# Sheet1.net
KiCad netlist of a schematic drawn in Altium Designer
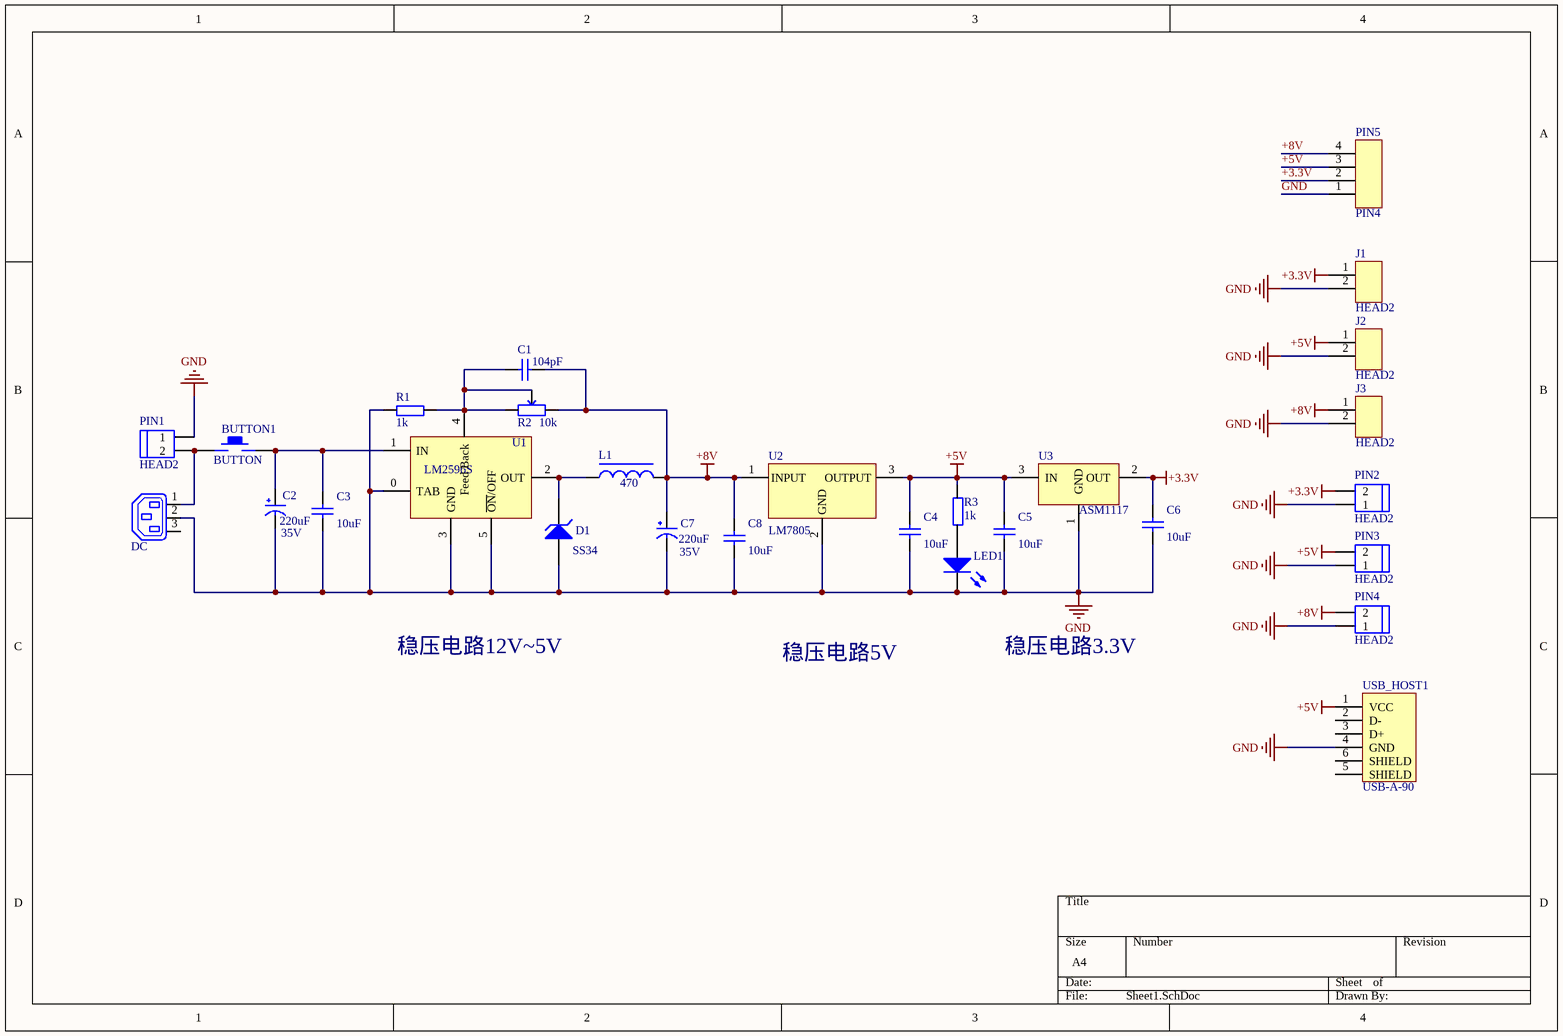
[diagram p0: Sheet1.SchDoc]

(export (version "E")
  (design (tool "Eeschema 10.0.6"))
  (components
    (comp (ref "BUTTON1")
      (value "BUTTON")
      (footprint "BOUTTON")
      (description "船式开关(KCD11 两档2脚)")
      (libsource (lib "STM32F429") (part "BUTTON"))
    )
    (comp (ref "C1")
      (value "104pF")
      (footprint "C-0805")
      (description "0805电容")
      (fields (field (name "Comment") "C_0805") (field (name "PUBLISHER") "Altium Limited"))
      (libsource (lib "Schlib1") (part "C_0805"))
    )
    (comp (ref "C2")
      (value "220uF")
      (footprint "8mm CAP+")
      (description "电解电容 35V 220 uF (8*10.2)")
      (fields (field (name "VOLTAGE") "35V"))
      (libsource (lib "Schlib1") (part "CAP+  8MM_1"))
    )
    (comp (ref "C3")
      (value "10uF")
      (footprint "C-0805")
      (description "0805电容")
      (fields (field (name "Comment") "C_0805") (field (name "PUBLISHER") "Altium Limited"))
      (libsource (lib "Schlib1") (part "C_0805"))
    )
    (comp (ref "C4")
      (value "10uF")
      (footprint "C-0805")
      (description "0805电容")
      (fields (field (name "Comment") "C_0805") (field (name "PUBLISHER") "Altium Limited"))
      (libsource (lib "Schlib1") (part "C_0805"))
    )
    (comp (ref "C5")
      (value "10uF")
      (footprint "C-0805")
      (description "0805电容")
      (fields (field (name "Comment") "C_0805") (field (name "PUBLISHER") "Altium Limited"))
      (libsource (lib "Schlib1") (part "C_0805"))
    )
    (comp (ref "C6")
      (value "10uF")
      (footprint "C-0805")
      (description "0805电容")
      (fields (field (name "Comment") "C_0805") (field (name "PUBLISHER") "Altium Limited"))
      (libsource (lib "Schlib1") (part "C_0805"))
    )
    (comp (ref "C7")
      (value "220uF")
      (footprint "8mm CAP+")
      (description "电解电容 35V 220 uF (8*10.2)")
      (fields (field (name "VOLTAGE") "35V"))
      (libsource (lib "Schlib1") (part "CAP+  8MM_1"))
    )
    (comp (ref "C8")
      (value "10uF")
      (footprint "C-0805")
      (description "0805电容")
      (fields (field (name "Comment") "C_0805") (field (name "PUBLISHER") "Altium Limited"))
      (libsource (lib "Schlib1") (part "C_0805"))
    )
    (comp (ref "D1")
      (value "SS34")
      (footprint "Diode-SS14")
      (description "稳压二极管 SS34（214A）")
      (fields (field (name "PUBLISHER") "Altium Limited"))
      (libsource (lib "Schlib1") (part "D Zener"))
    )
    (comp (ref "DC1")
      (value "DC")
      (footprint "DC-DC接口")
      (description "DC 电源插座 (5.5-2.1)")
      (libsource (lib "STM32F429") (part "DC"))
    )
    (comp (ref "J1")
      (value "HEAD2")
      (footprint "HEARD2")
      (description "2pin的连接键")
      (libsource (lib "SchlibCreativeDesign") (part "HEAD2"))
    )
    (comp (ref "J2")
      (value "HEAD2")
      (footprint "HEARD2")
      (description "2pin的连接键")
      (libsource (lib "SchlibCreativeDesign") (part "HEAD2"))
    )
    (comp (ref "J3")
      (value "HEAD2")
      (footprint "HEARD2")
      (description "2pin的连接键")
      (libsource (lib "SchlibCreativeDesign") (part "HEAD2"))
    )
    (comp (ref "L1")
      (value "470")
      (footprint "L")
      (description "Inductor")
      (fields (field (name "PUBLISHER") "Altium Limited"))
      (libsource (lib "Schlib1") (part "L"))
    )
    (comp (ref "LED1")
      (value "LED_0805")
      (footprint "LED-0805")
      (description "0805-LED")
      (fields (field (name "PUBLISHER") "Altium Limited"))
      (libsource (lib "Schlib1") (part "LED 0805"))
    )
    (comp (ref "PIN1")
      (value "HEAD2")
      (footprint "2PIN")
      (description "接线端子(KF301 2P)")
      (libsource (lib "STM32F429") (part "HEAD2"))
    )
    (comp (ref "PIN2") (value "HEAD2") (footprint "2PIN") (libsource (lib "STM32F429") (part "HEAD2")))
    (comp (ref "PIN3") (value "HEAD2") (footprint "2PIN") (libsource (lib "STM32F429") (part "HEAD2")))
    (comp (ref "PIN4") (value "HEAD2") (footprint "2PIN") (libsource (lib "STM32F429") (part "HEAD2")))
    (comp (ref "PIN5") (value "PIN4") (footprint "HDR4") (libsource (lib "Schlib1") (part "PIN4")))
    (comp (ref "R1")
      (value "1k")
      (footprint "R-0805")
      (description "0805电阻")
      (fields (field (name "Comment") "0805"))
      (libsource (lib "Schlib1") (part "R_0805"))
    )
    (comp (ref "R2")
      (value "10k")
      (footprint "RESPACK")
      (description "3296W电位器")
      (fields (field (name "Comment") "Slide rheostat"))
      (libsource (lib "Schlib1") (part "Slide rheostat"))
    )
    (comp (ref "R3")
      (value "1k")
      (footprint "R-0805")
      (description "0805电阻")
      (fields (field (name "Comment") "0805"))
      (libsource (lib "Schlib1") (part "R_0805"))
    )
    (comp (ref "U1")
      (value "LM2596S")
      (footprint "LM2596S")
      (description "LM2596S稳压芯片")
      (libsource (lib "Schlib1") (part "LM2596S_1"))
    )
    (comp (ref "U2")
      (value "LM7805")
      (footprint "LM7805")
      (description "LM7805三端稳压芯片")
      (libsource (lib "Schlib1") (part "LM7805"))
    )
    (comp (ref "U3")
      (value "ASM1117")
      (footprint "ASM1117")
      (description "ASM1117三端稳压芯片")
      (libsource (lib "Schlib1") (part "ASM1117"))
    )
    (comp (ref "USB_HOST1")
      (value "USB-A-90")
      (footprint "USB-A-90")
      (libsource (lib "ThirdShaft") (part "USB_A_90_1"))
    )
  )
  (nets
    (net (code "1") (name "+3.3V") (class "Default")
      (node (ref "C6") (pin "2") (pinfunction "2_2") (pintype "passive"))
      (node (ref "J1") (pin "1") (pinfunction "1_1") (pintype "passive"))
      (node (ref "PIN2") (pin "2") (pinfunction "2_2") (pintype "passive"))
      (node (ref "PIN5") (pin "2") (pinfunction "2_2") (pintype "passive"))
      (node (ref "U3") (pin "2") (pinfunction "OUT_2") (pintype "passive"))
    )
    (net (code "2") (name "+5V") (class "Default")
      (node (ref "C4") (pin "2") (pinfunction "2_2") (pintype "passive"))
      (node (ref "C5") (pin "2") (pinfunction "2_2") (pintype "passive"))
      (node (ref "J2") (pin "1") (pinfunction "1_1") (pintype "passive"))
      (node (ref "PIN3") (pin "2") (pinfunction "2_2") (pintype "passive"))
      (node (ref "PIN5") (pin "3") (pinfunction "3_3") (pintype "passive"))
      (node (ref "R3") (pin "2") (pintype "passive"))
      (node (ref "U2") (pin "3") (pinfunction "OUTPUT_3") (pintype "passive"))
      (node (ref "U3") (pin "3") (pinfunction "IN_3") (pintype "passive"))
      (node (ref "USB_HOST1") (pin "1") (pinfunction "VCC_1") (pintype "passive"))
    )
    (net (code "3") (name "+8V") (class "Default")
      (node (ref "C1") (pin "1") (pinfunction "1_1") (pintype "passive"))
      (node (ref "C7") (pin "1") (pinfunction "VCC_1") (pintype "passive"))
      (node (ref "C8") (pin "2") (pinfunction "2_2") (pintype "passive"))
      (node (ref "J3") (pin "1") (pinfunction "1_1") (pintype "passive"))
      (node (ref "L1") (pin "2") (pinfunction "2_2") (pintype "passive"))
      (node (ref "PIN4") (pin "2") (pinfunction "2_2") (pintype "passive"))
      (node (ref "PIN5") (pin "4") (pinfunction "4_4") (pintype "passive"))
      (node (ref "R2") (pin "3") (pinfunction "3_3") (pintype "passive"))
      (node (ref "U2") (pin "1") (pinfunction "INPUT_1") (pintype "passive"))
    )
    (net (code "4") (name "GND") (class "Default")
      (node (ref "C2") (pin "2") (pinfunction "GND_2") (pintype "passive"))
      (node (ref "C3") (pin "1") (pinfunction "1_1") (pintype "passive"))
      (node (ref "C4") (pin "1") (pinfunction "1_1") (pintype "passive"))
      (node (ref "C5") (pin "1") (pinfunction "1_1") (pintype "passive"))
      (node (ref "C6") (pin "1") (pinfunction "1_1") (pintype "passive"))
      (node (ref "C7") (pin "2") (pinfunction "GND_2") (pintype "passive"))
      (node (ref "C8") (pin "1") (pinfunction "1_1") (pintype "passive"))
      (node (ref "D1") (pin "1") (pinfunction "A_1") (pintype "passive"))
      (node (ref "DC1") (pin "2") (pinfunction "-_2") (pintype "power_in"))
      (node (ref "J1") (pin "2") (pinfunction "2_2") (pintype "passive"))
      (node (ref "J2") (pin "2") (pinfunction "2_2") (pintype "passive"))
      (node (ref "J3") (pin "2") (pinfunction "2_2") (pintype "passive"))
      (node (ref "LED1") (pin "2") (pinfunction "2_2") (pintype "passive"))
      (node (ref "PIN1") (pin "1") (pinfunction "1_1") (pintype "passive"))
      (node (ref "PIN2") (pin "1") (pinfunction "1_1") (pintype "passive"))
      (node (ref "PIN3") (pin "1") (pinfunction "1_1") (pintype "passive"))
      (node (ref "PIN4") (pin "1") (pinfunction "1_1") (pintype "passive"))
      (node (ref "PIN5") (pin "1") (pinfunction "1_1") (pintype "passive"))
      (node (ref "R1") (pin "1") (pintype "passive"))
      (node (ref "U1") (pin "0") (pinfunction "TAB_0") (pintype "power_in"))
      (node (ref "U1") (pin "3") (pinfunction "GND_3") (pintype "power_in"))
      (node (ref "U1") (pin "5") (pinfunction "~{ON}/OFF_5") (pintype "power_in"))
      (node (ref "U2") (pin "2") (pinfunction "GND_2") (pintype "passive"))
      (node (ref "U3") (pin "1") (pinfunction "GND_1") (pintype "passive"))
      (node (ref "USB_HOST1") (pin "4") (pinfunction "GND_4") (pintype "passive"))
    )
    (net (code "5") (name "Net-(C2-VCC)") (class "Default")
      (node (ref "BUTTON1") (pin "2") (pinfunction "2_2") (pintype "passive"))
      (node (ref "C2") (pin "1") (pinfunction "VCC_1") (pintype "passive"))
      (node (ref "C3") (pin "2") (pinfunction "2_2") (pintype "passive"))
      (node (ref "U1") (pin "1") (pinfunction "IN_1") (pintype "passive"))
    )
    (net (code "6") (name "Net-(D1-K)") (class "Default")
      (node (ref "D1") (pin "2") (pinfunction "K_2") (pintype "passive"))
      (node (ref "L1") (pin "1") (pinfunction "1_1") (pintype "passive"))
      (node (ref "U1") (pin "2") (pinfunction "OUT_2") (pintype "passive"))
    )
    (net (code "7") (name "Net-(DC1-+)") (class "Default")
      (node (ref "BUTTON1") (pin "1") (pinfunction "1_1") (pintype "passive"))
      (node (ref "DC1") (pin "1") (pinfunction "+_1") (pintype "power_in"))
      (node (ref "PIN1") (pin "2") (pinfunction "2_2") (pintype "passive"))
    )
    (net (code "8") (name "Net-(LED1-Pad1)") (class "Default")
      (node (ref "LED1") (pin "1") (pinfunction "1_1") (pintype "passive"))
      (node (ref "R3") (pin "1") (pintype "passive"))
    )
    (net (code "9") (name "Net-(U1-Feed_Back)") (class "Default")
      (node (ref "C1") (pin "2") (pinfunction "2_2") (pintype "passive"))
      (node (ref "R1") (pin "2") (pintype "passive"))
      (node (ref "R2") (pin "1") (pinfunction "1_1") (pintype "passive"))
      (node (ref "R2") (pin "2") (pinfunction "2_2") (pintype "passive"))
      (node (ref "U1") (pin "4") (pinfunction "Feed_Back_4") (pintype "power_in"))
    )
    (net (code "10") (name "unconnected-(DC1---Pad3)") (class "Default")
      (node (ref "DC1") (pin "3") (pinfunction "-_3") (pintype "power_in"))
    )
    (net (code "11") (name "unconnected-(USB_HOST1-D+-Pad3)") (class "Default")
      (node (ref "USB_HOST1") (pin "3") (pinfunction "D+_3") (pintype "passive"))
    )
    (net (code "12") (name "unconnected-(USB_HOST1-D--Pad2)") (class "Default")
      (node (ref "USB_HOST1") (pin "2") (pinfunction "D-_2") (pintype "passive"))
    )
    (net (code "13") (name "unconnected-(USB_HOST1-SHIELD-Pad5)") (class "Default")
      (node (ref "USB_HOST1") (pin "5") (pinfunction "SHIELD_5") (pintype "passive"))
    )
    (net (code "14") (name "unconnected-(USB_HOST1-SHIELD-Pad6)") (class "Default")
      (node (ref "USB_HOST1") (pin "6") (pinfunction "SHIELD_6") (pintype "passive"))
    )
  )
)
